# System.net
KiCad netlist of a schematic drawn in Altium Designer
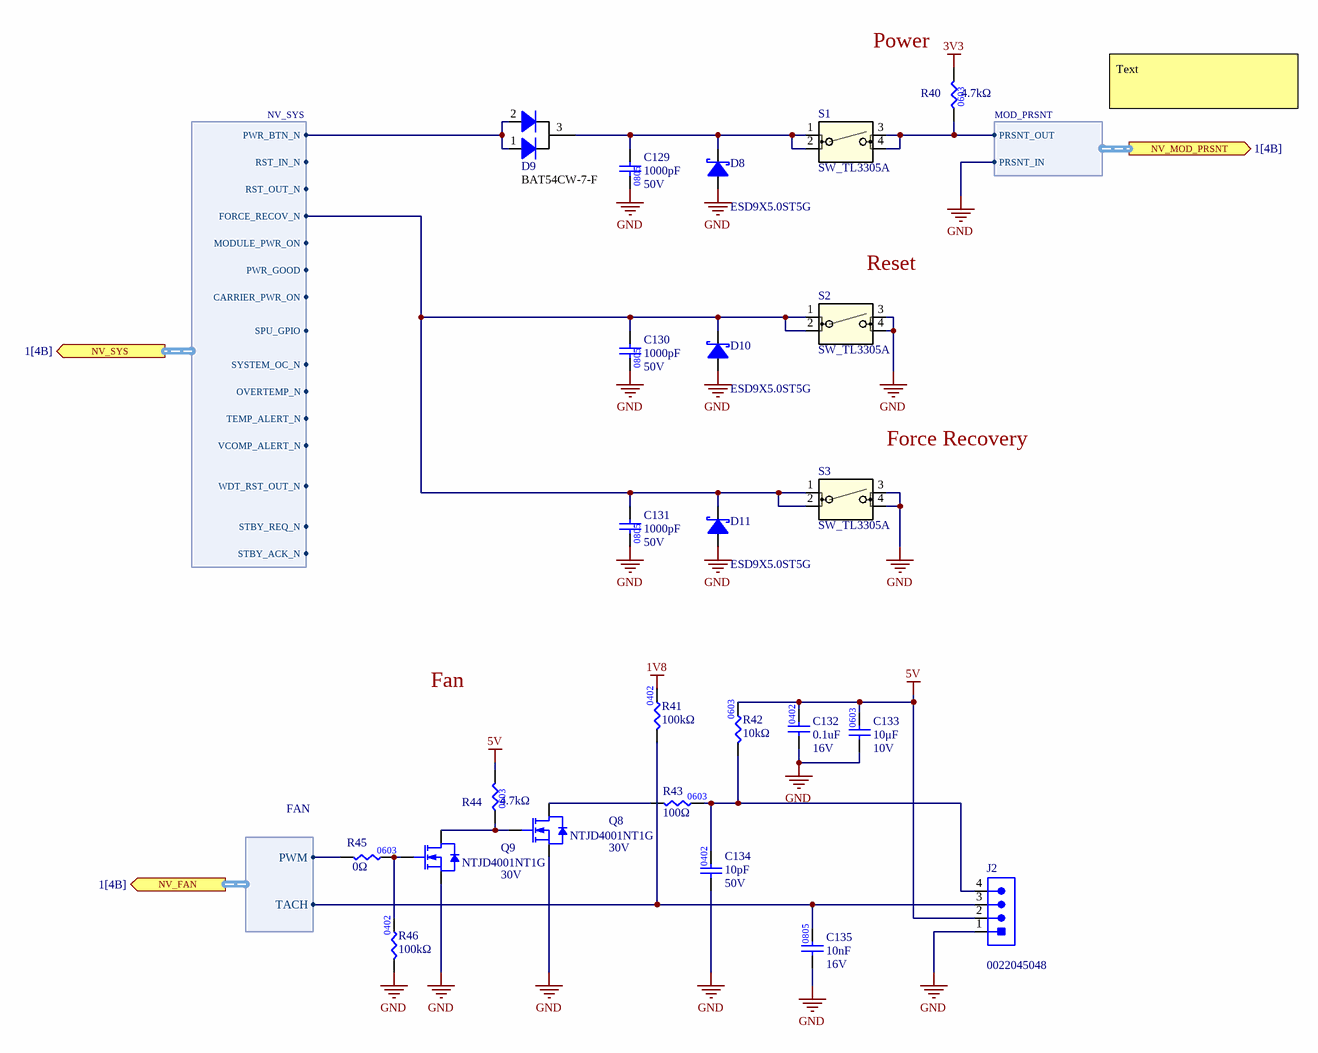
[diagram p0: System.SchDoc]

(export (version "E")
  (design (tool "Eeschema 10.0.6"))
  (components
    (comp (ref "C129")
      (value "1000pF")
      (footprint "CAP2012")
      (description "CAP CER 1000pF 50V X7R 0805")
      (fields (field (name "VOLTAGE RATING") "50V") (field (name "Comment") "CAP_1000pF_50V_0805"))
      (libsource (lib "UWRT_Schematic_Library_2020") (part "CAP_1000pF_50V_0805"))
    )
    (comp (ref "C130")
      (value "1000pF")
      (footprint "CAP2012")
      (description "CAP CER 1000pF 50V X7R 0805")
      (fields (field (name "VOLTAGE RATING") "50V") (field (name "Comment") "CAP_1000pF_50V_0805"))
      (libsource (lib "UWRT_Schematic_Library_2020") (part "CAP_1000pF_50V_0805"))
    )
    (comp (ref "C131")
      (value "1000pF")
      (footprint "CAP2012")
      (description "CAP CER 1000pF 50V X7R 0805")
      (fields (field (name "VOLTAGE RATING") "50V") (field (name "Comment") "CAP_1000pF_50V_0805"))
      (libsource (lib "UWRT_Schematic_Library_2020") (part "CAP_1000pF_50V_0805"))
    )
    (comp (ref "C132")
      (value "CAP_0.1uF_16V_X7R_0402")
      (footprint "CAP0402")
      (description "Ceramic Capacitor, Ceramic")
      (fields
        (field (name "MANUFACTURER") "Taiyo Yuden")
        (field (name "MANUFACTURER PART NUMBER") "LMK212AC6106MD-T")
        (field (name "RATED DC VOLTAGE (URDC)") "16V")
        (field (name "CAPACITANCE") "0.1uF")
      )
      (libsource (lib "UWRT_Schematic_Library_2020") (part "CAP_0.1uF_16V_X7R_0402"))
    )
    (comp (ref "C133")
      (value "10μF")
      (footprint "CAP0603")
      (description "CAP CER 10UF 10V X5R 0603")
      (fields (field (name "VOLTAGE RATING") "10V") (field (name "Comment") "CAP_10uF_10V_0603"))
      (libsource (lib "UWRT_Schematic_Library_2020") (part "CAP_10uF_10V_0603"))
    )
    (comp (ref "C134")
      (value "CAP_10pF_50V_0402")
      (footprint "CAP0402")
      (fields (field (name "CAPACITANCE") "10pF") (field (name "VOLTAGE") "50V"))
      (libsource (lib "UWRT_Schematic_Library_2020") (part "CAP_10pF_50V_0402"))
    )
    (comp (ref "C135")
      (value "10nF")
      (footprint "CAP2012")
      (description "CAP CER 10000PF 16V X7R 0805")
      (fields (field (name "VOLTAGE RATING") "16V") (field (name "Comment") "CAP_10nF_16V_0805"))
      (libsource (lib "UWRT_Schematic_Library_2020") (part "CAP_10nF_16V_0805"))
    )
    (comp (ref "D8")
      (value "TVS_DIODE_UNIDIR_5V")
      (footprint "SOD-923")
      (description "TVS DIODE 5VWM 12.3VC SOD923")
      (fields (field (name "MANUFACTURER PART NUMBER 1") "ESD9X5.0ST5G"))
      (libsource (lib "UWRT_Schematic_Library_2020") (part "TVS_DIODE_UNIDIR_5V"))
    )
    (comp (ref "D9")
      (value "BAT54CW-7-F")
      (footprint "SOT323")
      (description "Diode Array 1 Pair Common Cathode Schottky 30 V 200mA (DC) Surface Mount SC-70, SOT-323")
      (fields
        (field (name "MANUFACTURER_PART_NUMBER") "BAT54CW-7-F")
        (field (name "COPYRIGHT") "Copyright (C) 2016 Accelerated Designs. All rights reserved")
      )
      (libsource (lib "UWRT_Schematic_Library_2020") (part "DIODE_30V_SOT323"))
    )
    (comp (ref "D10")
      (value "TVS_DIODE_UNIDIR_5V")
      (footprint "SOD-923")
      (description "TVS DIODE 5VWM 12.3VC SOD923")
      (fields (field (name "MANUFACTURER PART NUMBER 1") "ESD9X5.0ST5G"))
      (libsource (lib "UWRT_Schematic_Library_2020") (part "TVS_DIODE_UNIDIR_5V"))
    )
    (comp (ref "D11")
      (value "TVS_DIODE_UNIDIR_5V")
      (footprint "SOD-923")
      (description "TVS DIODE 5VWM 12.3VC SOD923")
      (fields (field (name "MANUFACTURER PART NUMBER 1") "ESD9X5.0ST5G"))
      (libsource (lib "UWRT_Schematic_Library_2020") (part "TVS_DIODE_UNIDIR_5V"))
    )
    (comp (ref "J2")
      (value "CON_4POS")
      (description "CONN HEADER VERT 4POS 2.54MM")
      (fields (field (name "MANUFACTURER") "Molex") (field (name "MANUFACTURER PART NUMBER") "0022045048"))
      (libsource (lib "UWRT_Schematic_Library_2020") (part "CON_4POS"))
    )
    (comp (ref "Q8")
      (value "NMOS_30V_0.25A")
      (footprint "SOT363")
      (description "MOSFET 2N-CH 30V 0.25A SOT-363")
      (fields
        (field (name "DS BREAKDOWN VOLTAGE-MIN") "30V")
        (field (name "MANUFACTURER PART NUMBER 1") "NTJD4001NT1G")
      )
      (libsource (lib "UWRT_Schematic_Library_2020") (part "NMOS_30V_0.25A"))
    )
    (comp (ref "Q9")
      (value "NMOS_30V_0.25A")
      (footprint "SOT363")
      (description "MOSFET 2N-CH 30V 0.25A SOT-363")
      (fields
        (field (name "DS BREAKDOWN VOLTAGE-MIN") "30V")
        (field (name "MANUFACTURER PART NUMBER 1") "NTJD4001NT1G")
      )
      (libsource (lib "UWRT_Schematic_Library_2020") (part "NMOS_30V_0.25A"))
    )
    (comp (ref "R40")
      (value "4.7kΩ")
      (footprint "RES0603")
      (description "RES 4.7K OHM 5% 1/10W 0603")
      (fields (field (name "Comment") "RES_4.7kΩ_0603"))
      (libsource (lib "UWRT_Schematic_Library_2020") (part "RES_4.7kΩ_0603_5%"))
    )
    (comp (ref "R41")
      (value "100kΩ")
      (footprint "RES0402")
      (description "RES SMD 100K OHM 5% 1/10W 0402")
      (fields (field (name "POWER") "0.1W, 1/10W") (field (name "TOLERANCE") "5%"))
      (libsource (lib "UWRT_Schematic_Library_2020") (part "RES_100kΩ_0402_5%"))
    )
    (comp (ref "R42")
      (value "10kΩ")
      (footprint "RES0603")
      (description "RES 10K OHM 5% 1/10W 0603")
      (fields (field (name "Comment") "RES_10kΩ_0603_5%"))
      (libsource (lib "UWRT_Schematic_Library_2020") (part "RES_10kΩ_0603_5%"))
    )
    (comp (ref "R43")
      (value "100Ω")
      (footprint "RES0603")
      (description "RES 100 OHM 1% 1/10W 0603")
      (fields (field (name "Comment") "RES_100Ω_0603"))
      (libsource (lib "UWRT_Schematic_Library_2020") (part "RES_100Ω_0603_1%"))
    )
    (comp (ref "R44")
      (value "4.7kΩ")
      (footprint "RES0603")
      (description "RES 4.7K OHM 5% 1/10W 0603")
      (fields (field (name "Comment") "RES_4.7kΩ_0603"))
      (libsource (lib "UWRT_Schematic_Library_2020") (part "RES_4.7kΩ_0603_5%"))
    )
    (comp (ref "R45")
      (value "0Ω")
      (footprint "RES0603")
      (description "RES 0 OHM JUMPER 1/10W 0603")
      (fields (field (name "Comment") "RES_0Ω_0603"))
      (libsource (lib "UWRT_Schematic_Library_2020") (part "RES_0Ω_0603"))
    )
    (comp (ref "R46")
      (value "100kΩ")
      (footprint "RES0402")
      (description "RES SMD 100K OHM 5% 1/10W 0402")
      (fields (field (name "POWER") "0.1W, 1/10W") (field (name "TOLERANCE") "5%"))
      (libsource (lib "UWRT_Schematic_Library_2020") (part "RES_100kΩ_0402_5%"))
    )
    (comp (ref "S1")
      (value "SW_TL3305A")
      (footprint "SW_TL3305AF260QG")
      (description "TL3305A Series SPST 12 V 4.5 x 4.5 mm 260 gf Top Actuated SMT Tactile Switch")
      (fields (field (name "MANUFACTURER PART NUMBER") "TL3305AF260QG"))
      (libsource (lib "UWRT_Schematic_Library_2020") (part "SW_TL3305A"))
    )
    (comp (ref "S2")
      (value "SW_TL3305A")
      (footprint "SW_TL3305AF260QG")
      (description "TL3305A Series SPST 12 V 4.5 x 4.5 mm 260 gf Top Actuated SMT Tactile Switch")
      (fields (field (name "MANUFACTURER PART NUMBER") "TL3305AF260QG"))
      (libsource (lib "UWRT_Schematic_Library_2020") (part "SW_TL3305A"))
    )
    (comp (ref "S3")
      (value "SW_TL3305A")
      (footprint "SW_TL3305AF260QG")
      (description "TL3305A Series SPST 12 V 4.5 x 4.5 mm 260 gf Top Actuated SMT Tactile Switch")
      (fields (field (name "MANUFACTURER PART NUMBER") "TL3305AF260QG"))
      (libsource (lib "UWRT_Schematic_Library_2020") (part "SW_TL3305A"))
    )
  )
  (nets
    (net (code "4") (name "/FORCE_RECOV_N") (class "Default")
      (node (ref "C130") (pin "2") (pinfunction "2_2") (pintype "passive"))
      (node (ref "C131") (pin "2") (pinfunction "2_2") (pintype "passive"))
      (node (ref "D10") (pin "2") (pinfunction "Cathode_2") (pintype "passive"))
      (node (ref "D11") (pin "2") (pinfunction "Cathode_2") (pintype "passive"))
      (node (ref "S2") (pin "1") (pinfunction "1_1") (pintype "passive"))
      (node (ref "S2") (pin "2") (pinfunction "2_2") (pintype "passive"))
      (node (ref "S3") (pin "1") (pinfunction "1_1") (pintype "passive"))
      (node (ref "S3") (pin "2") (pinfunction "2_2") (pintype "passive"))
    )
    (net (code "5") (name "/PRSNT_OUT") (class "Default")
      (node (ref "R40") (pin "1") (pinfunction "1_1") (pintype "passive"))
      (node (ref "S1") (pin "3") (pinfunction "3_3") (pintype "passive"))
      (node (ref "S1") (pin "4") (pinfunction "4_4") (pintype "passive"))
    )
    (net (code "6") (name "/PWM") (class "Default")
      (node (ref "R45") (pin "1") (pinfunction "1_1") (pintype "passive"))
    )
    (net (code "7") (name "/PWR_BTN_N") (class "Default")
      (node (ref "D9") (pin "1") (pintype "passive"))
      (node (ref "D9") (pin "2") (pinfunction "2_2") (pintype "passive"))
    )
    (net (code "8") (name "/TACH") (class "Default")
      (node (ref "C135") (pin "2") (pinfunction "2_2") (pintype "passive"))
      (node (ref "J2") (pin "3") (pinfunction "3_3") (pintype "passive"))
      (node (ref "R41") (pin "1") (pinfunction "1_1") (pintype "passive"))
    )
    (net (code "12") (name "1V8") (class "Default")
      (node (ref "R41") (pin "2") (pinfunction "2_2") (pintype "passive"))
    )
    (net (code "13") (name "3V3") (class "Default")
      (node (ref "R40") (pin "2") (pinfunction "2_2") (pintype "passive"))
    )
    (net (code "14") (name "5V") (class "Default")
      (node (ref "C132") (pin "2") (pinfunction "2_2") (pintype "passive"))
      (node (ref "C133") (pin "2") (pinfunction "2_2") (pintype "passive"))
      (node (ref "J2") (pin "2") (pinfunction "2_2") (pintype "passive"))
      (node (ref "R42") (pin "2") (pinfunction "2_2") (pintype "passive"))
      (node (ref "R44") (pin "2") (pinfunction "2_2") (pintype "passive"))
    )
    (net (code "15") (name "GND") (class "Default")
      (node (ref "C129") (pin "1") (pinfunction "1_1") (pintype "passive"))
      (node (ref "C130") (pin "1") (pinfunction "1_1") (pintype "passive"))
      (node (ref "C131") (pin "1") (pinfunction "1_1") (pintype "passive"))
      (node (ref "C132") (pin "1") (pinfunction "1_1") (pintype "passive"))
      (node (ref "C133") (pin "1") (pinfunction "1_1") (pintype "passive"))
      (node (ref "C134") (pin "1") (pinfunction "1_1") (pintype "passive"))
      (node (ref "C135") (pin "1") (pinfunction "1_1") (pintype "passive"))
      (node (ref "D10") (pin "1") (pinfunction "Anode_1") (pintype "passive"))
      (node (ref "D11") (pin "1") (pinfunction "Anode_1") (pintype "passive"))
      (node (ref "D8") (pin "1") (pinfunction "Anode_1") (pintype "passive"))
      (node (ref "J2") (pin "1") (pintype "passive"))
      (node (ref "Q8") (pin "2") (pinfunction "SOURCE_2") (pintype "passive"))
      (node (ref "Q9") (pin "2") (pinfunction "SOURCE_2") (pintype "passive"))
      (node (ref "R46") (pin "1") (pinfunction "1_1") (pintype "passive"))
      (node (ref "S2") (pin "3") (pinfunction "3_3") (pintype "passive"))
      (node (ref "S2") (pin "4") (pinfunction "4_4") (pintype "passive"))
      (node (ref "S3") (pin "3") (pinfunction "3_3") (pintype "passive"))
      (node (ref "S3") (pin "4") (pinfunction "4_4") (pintype "passive"))
    )
    (net (code "16") (name "Net-(C134-Pad2)") (class "Default")
      (node (ref "C134") (pin "2") (pinfunction "2_2") (pintype "passive"))
      (node (ref "J2") (pin "4") (pinfunction "4_4") (pintype "passive"))
      (node (ref "R42") (pin "1") (pinfunction "1_1") (pintype "passive"))
      (node (ref "R43") (pin "2") (pinfunction "2_2") (pintype "passive"))
    )
    (net (code "17") (name "Net-(D8-Cathode)") (class "Default")
      (node (ref "C129") (pin "2") (pinfunction "2_2") (pintype "passive"))
      (node (ref "D8") (pin "2") (pinfunction "Cathode_2") (pintype "passive"))
      (node (ref "S1") (pin "1") (pinfunction "1_1") (pintype "passive"))
      (node (ref "S1") (pin "2") (pinfunction "2_2") (pintype "passive"))
    )
    (net (code "18") (name "Net-(D9-Pad3)_1") (class "Default")
      (node (ref "D9") (pin "3") (pintype "passive"))
    )
    (net (code "19") (name "Net-(D9-Pad3)_2") (class "Default")
      (node (ref "D9") (pin "3") (pintype "passive"))
    )
    (net (code "20") (name "Net-(Q8-DRAIN)") (class "Default")
      (node (ref "Q8") (pin "3") (pinfunction "DRAIN_3") (pintype "passive"))
      (node (ref "R43") (pin "1") (pinfunction "1_1") (pintype "passive"))
    )
    (net (code "21") (name "Net-(Q8-GATE)") (class "Default")
      (node (ref "Q8") (pin "1") (pinfunction "GATE_1") (pintype "passive"))
      (node (ref "Q9") (pin "3") (pinfunction "DRAIN_3") (pintype "passive"))
      (node (ref "R44") (pin "1") (pinfunction "1_1") (pintype "passive"))
    )
    (net (code "22") (name "Net-(Q9-GATE)") (class "Default")
      (node (ref "Q9") (pin "1") (pinfunction "GATE_1") (pintype "passive"))
      (node (ref "R45") (pin "2") (pinfunction "2_2") (pintype "passive"))
      (node (ref "R46") (pin "2") (pinfunction "2_2") (pintype "passive"))
    )
    (net (code "23") (name "unconnected-(D9-Pad3)") (class "Default")
      (node (ref "D9") (pin "3") (pintype "passive"))
    )
  )
)
